# RTC.net
KiCad netlist of a schematic drawn in Altium Designer
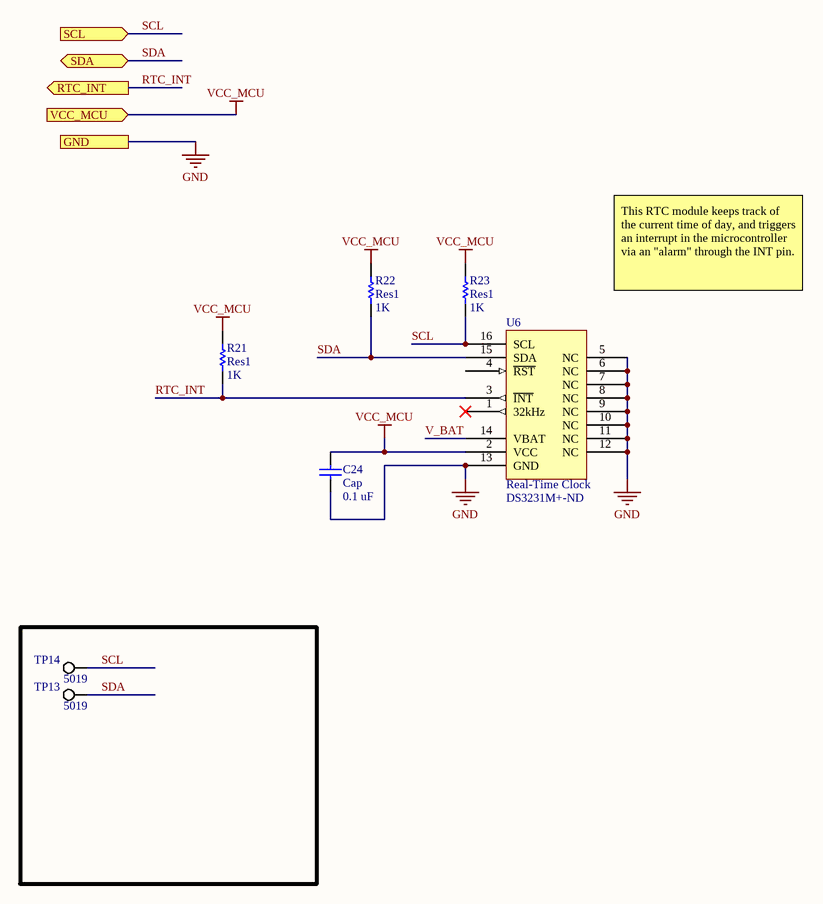
[diagram p0: RTC.SchDoc]

(export (version "E")
  (design (tool "Eeschema 10.0.6"))
  (components
    (comp (ref "C24")
      (value "Cap")
      (footprint "1608[0603]")
      (description "Capacitor")
      (fields (field (name "ALTIUM_VALUE") "0.1 uF") (field (name "PUBLISHER") "Altium Limited"))
      (libsource (lib "Miscellaneous Devices") (part "Cap"))
    )
    (comp (ref "R21")
      (value "Res1")
      (footprint "J1-0603")
      (description "Resistor")
      (fields (field (name "ALTIUM_VALUE") "1K") (field (name "PUBLISHER") "Altium Limited"))
      (libsource (lib "Miscellaneous Devices") (part "Res1"))
    )
    (comp (ref "R22")
      (value "Res1")
      (footprint "J1-0603")
      (description "Resistor")
      (fields (field (name "ALTIUM_VALUE") "1K") (field (name "PUBLISHER") "Altium Limited"))
      (libsource (lib "Miscellaneous Devices") (part "Res1"))
    )
    (comp (ref "R23")
      (value "Res1")
      (footprint "J1-0603")
      (description "Resistor")
      (fields (field (name "ALTIUM_VALUE") "1K") (field (name "PUBLISHER") "Altium Limited"))
      (libsource (lib "Miscellaneous Devices") (part "Res1"))
    )
    (comp (ref "TP13")
      (value "5019")
      (footprint "KSTN-5019_V")
      (description "Test Point, 1 Position SMD, RoHS, Tape and Reel")
      (libsource (lib "Altium Content Vault") (part "TESTPOINT_WHITE"))
    )
    (comp (ref "TP14")
      (value "5019")
      (footprint "KSTN-5019_V")
      (description "Test Point, 1 Position SMD, RoHS, Tape and Reel")
      (libsource (lib "Altium Content Vault") (part "TESTPOINT_WHITE"))
    )
    (comp (ref "U6")
      (value "Real-Time Clock")
      (footprint "DS3231 SO16")
      (description "Extremely Accurate I2C-Integrated RTC/TCXO/Crystal")
      (fields
        (field (name "MANUFACTURER") "Maxim")
        (field (name "MANUFACTURER PART NUMBER") "DS3231M+")
        (field (name "SUPPLIER PART NUMBER 1") "DS3231M+-ND")
      )
      (libsource (lib "Iot_Medicine") (part "DS3231"))
    )
  )
  (nets
    (net (code "1") (name "/RTC_INT") (class "Default")
      (node (ref "R21") (pin "1") (pinfunction "1_1") (pintype "passive"))
      (node (ref "U6") (pin "3") (pinfunction "~{INT}_3") (pintype "output"))
    )
    (net (code "2") (name "/SCL") (class "Default")
      (node (ref "R23") (pin "1") (pinfunction "1_1") (pintype "passive"))
      (node (ref "TP14") (pin "1") (pinfunction "1_1") (pintype "passive"))
      (node (ref "U6") (pin "16") (pinfunction "SCL_16") (pintype "open_collector"))
    )
    (net (code "3") (name "/SDA") (class "Default")
      (node (ref "R22") (pin "1") (pinfunction "1_1") (pintype "passive"))
      (node (ref "TP13") (pin "1") (pinfunction "1_1") (pintype "passive"))
      (node (ref "U6") (pin "15") (pinfunction "SDA_15") (pintype "open_collector"))
    )
    (net (code "4") (name "/V_BAT") (class "Default")
      (node (ref "U6") (pin "14") (pinfunction "VBAT_14") (pintype "power_in"))
    )
    (net (code "5") (name "GND") (class "Default")
      (node (ref "C24") (pin "2") (pinfunction "2_2") (pintype "passive"))
      (node (ref "U6") (pin "10") (pinfunction "NC_10") (pintype "passive"))
      (node (ref "U6") (pin "11") (pinfunction "NC_11") (pintype "passive"))
      (node (ref "U6") (pin "12") (pinfunction "NC_12") (pintype "passive"))
      (node (ref "U6") (pin "13") (pinfunction "GND_13") (pintype "power_in"))
      (node (ref "U6") (pin "5") (pinfunction "NC_5") (pintype "passive"))
      (node (ref "U6") (pin "6") (pinfunction "NC_6") (pintype "passive"))
      (node (ref "U6") (pin "7") (pinfunction "NC_7") (pintype "passive"))
      (node (ref "U6") (pin "8") (pinfunction "NC_8") (pintype "passive"))
      (node (ref "U6") (pin "9") (pinfunction "NC_9") (pintype "passive"))
    )
    (net (code "6") (name "VCC_MCU") (class "Default")
      (node (ref "C24") (pin "1") (pinfunction "1_1") (pintype "passive"))
      (node (ref "R21") (pin "2") (pinfunction "2_2") (pintype "passive"))
      (node (ref "R22") (pin "2") (pinfunction "2_2") (pintype "passive"))
      (node (ref "R23") (pin "2") (pinfunction "2_2") (pintype "passive"))
      (node (ref "U6") (pin "2") (pinfunction "VCC_2") (pintype "power_in"))
    )
    (net (code "7") (name "unconnected-(U6-32kHz-Pad1)") (class "Default")
      (node (ref "U6") (pin "1") (pinfunction "32kHz_1") (pintype "output+no_connect"))
    )
    (net (code "8") (name "unconnected-(U6-~{RST}-Pad4)") (class "Default")
      (node (ref "U6") (pin "4") (pinfunction "~{RST}_4") (pintype "input"))
    )
  )
)
